# ProPrj_RGB_Controller_2025-11-02.net
KiCad netlist of a schematic drawn in EasyEDA Pro
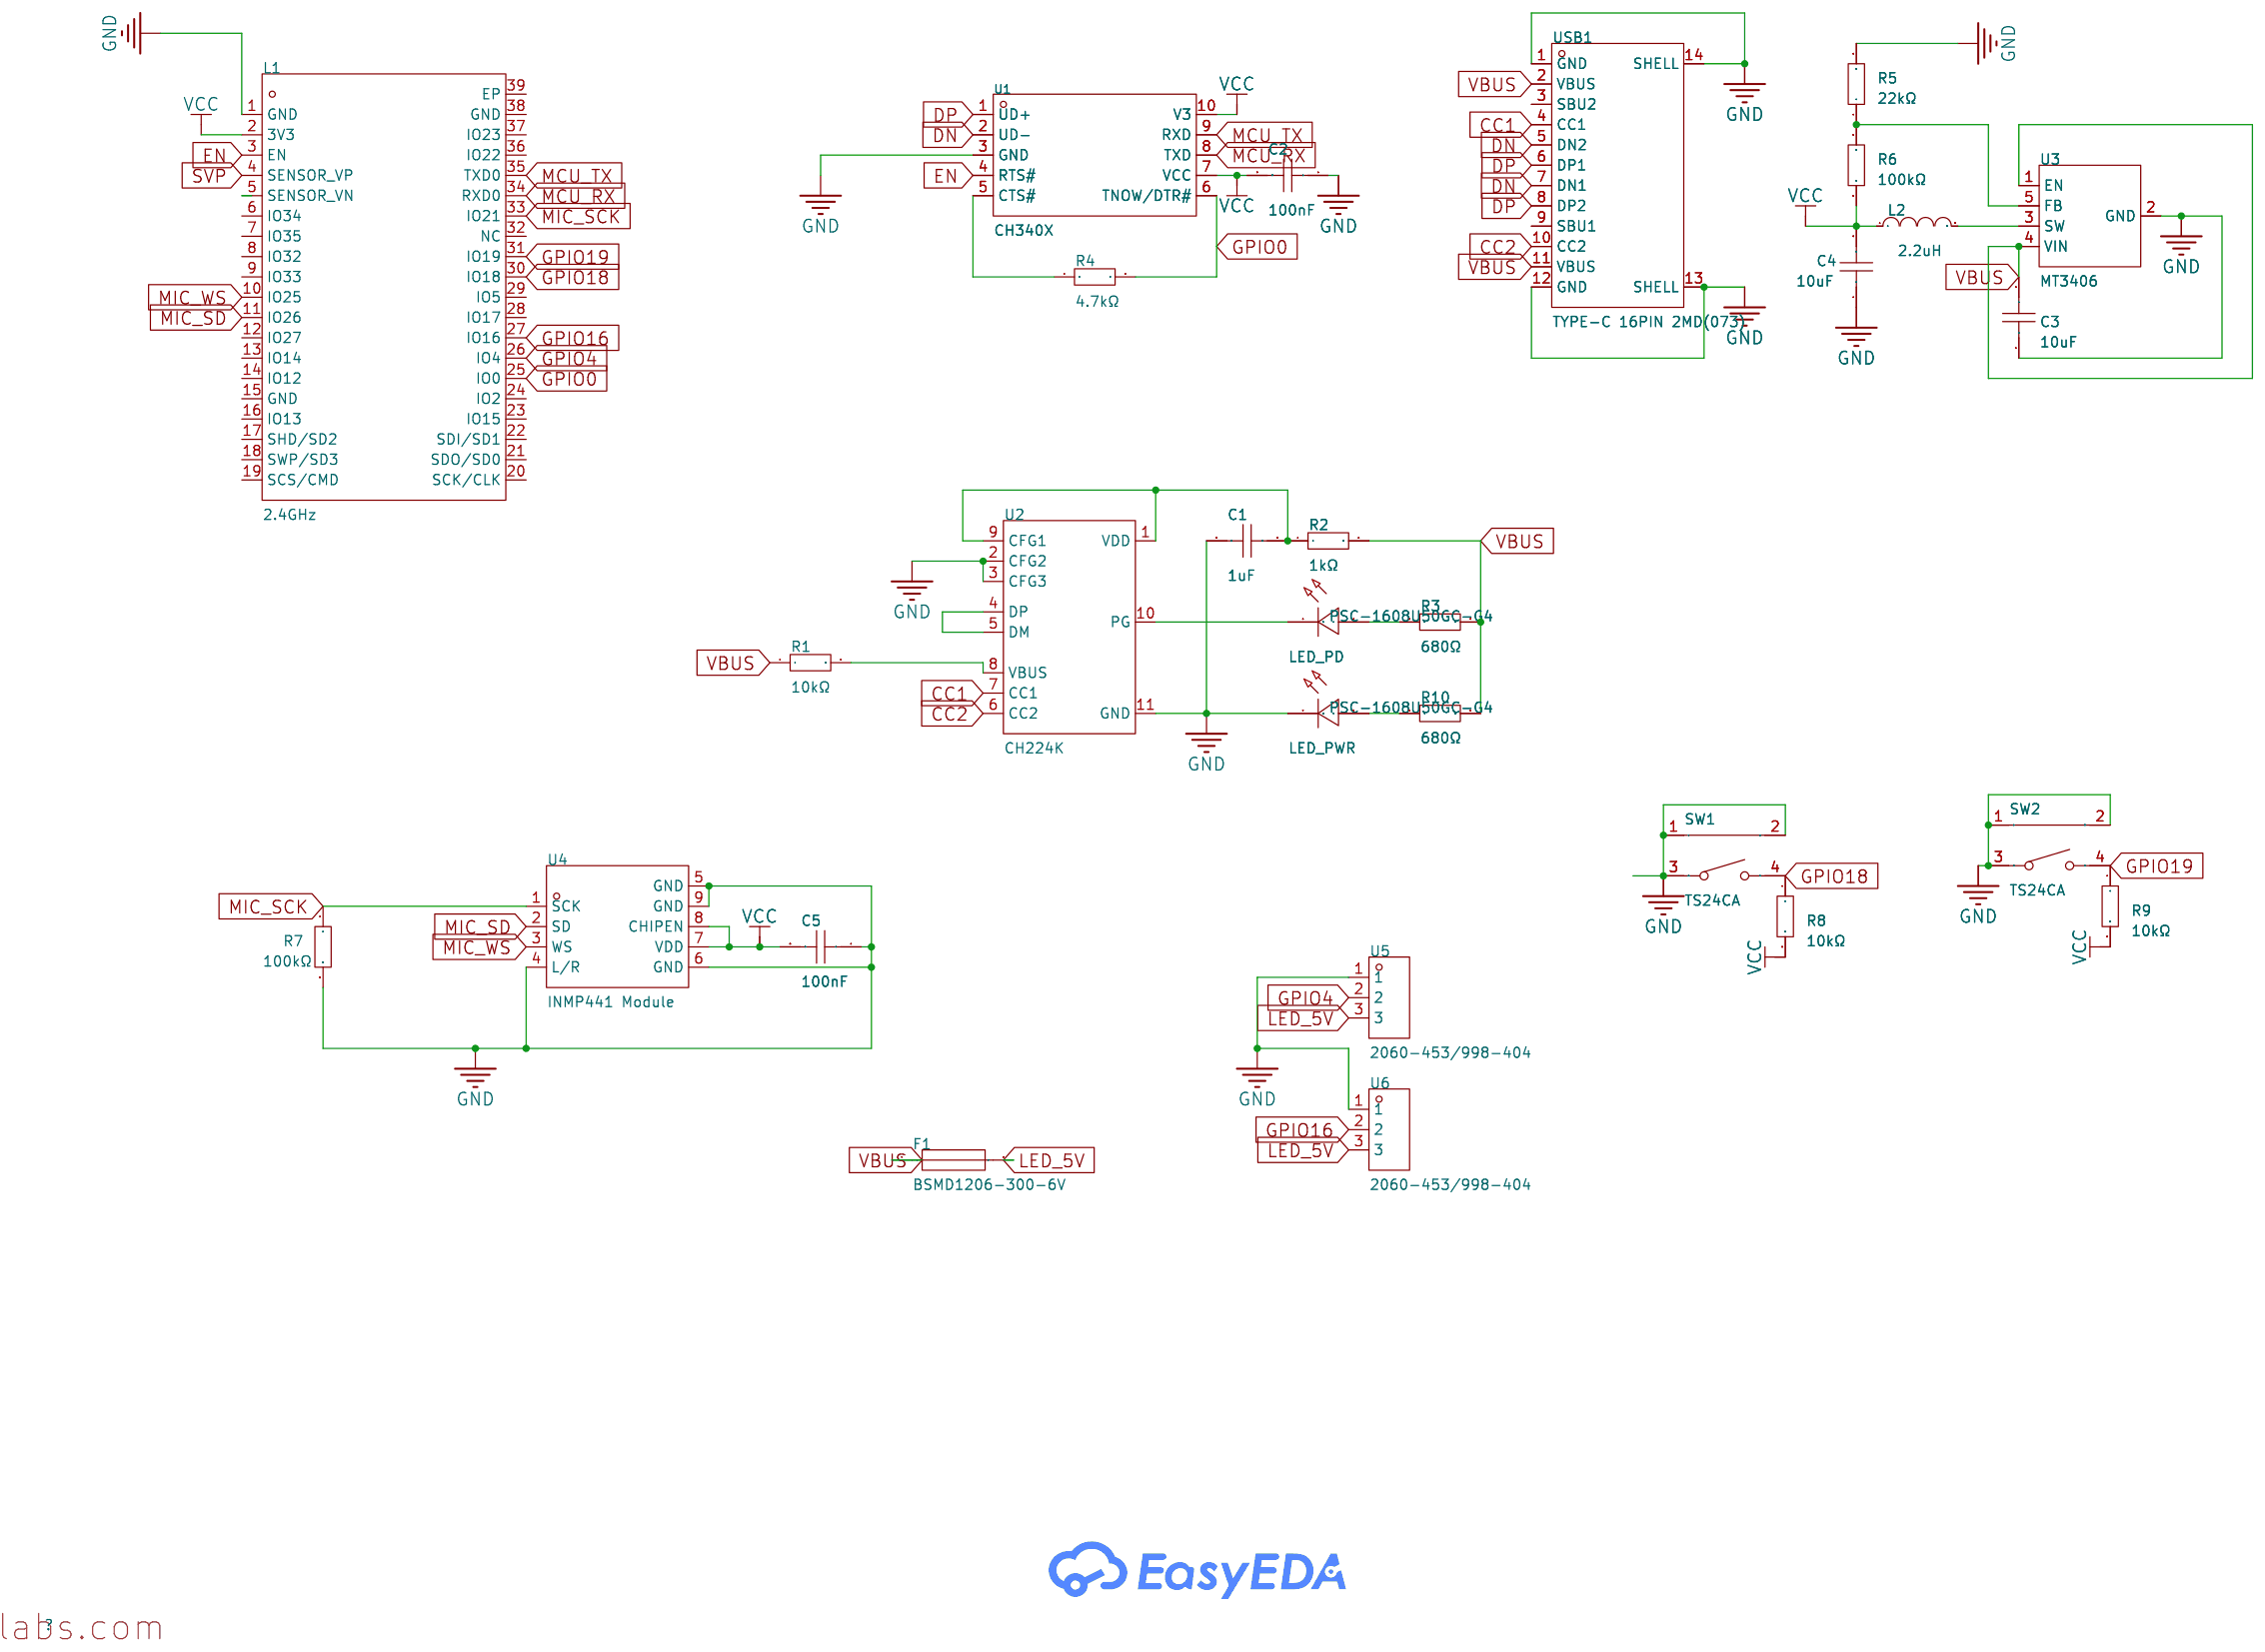
[diagram p0: schematic sheet]

(export (version "E")
  (design (tool "Eeschema 10.0.6"))
  (components
    (comp (ref "C1")
      (value "1uF")
      (footprint "easyedapro:C0603")
      (fields
        (field (name "Manufacturer Part") "CL05A105KO5NNNC")
        (field (name "Manufacturer") "SAMSUNG(三星)")
      )
      (libsource (lib "easyedapro") (part "CAP"))
    )
    (comp (ref "C2")
      (value "100nF")
      (footprint "easyedapro:C0603")
      (fields
        (field (name "Manufacturer Part") "CL05B104KO5NNNC")
        (field (name "Manufacturer") "SAMSUNG(三星)")
      )
      (libsource (lib "easyedapro") (part "CAP"))
    )
    (comp (ref "C3")
      (value "10uF")
      (footprint "easyedapro:C0603")
      (fields
        (field (name "Manufacturer Part") "CL10A106KP8NNNC")
        (field (name "Manufacturer") "SAMSUNG(三星)")
      )
      (libsource (lib "easyedapro") (part "CAP"))
    )
    (comp (ref "C4")
      (value "10uF")
      (footprint "easyedapro:C0603")
      (fields
        (field (name "Manufacturer Part") "CL10A106KP8NNNC")
        (field (name "Manufacturer") "SAMSUNG(三星)")
      )
      (libsource (lib "easyedapro") (part "CAP"))
    )
    (comp (ref "C5")
      (value "100nF")
      (footprint "easyedapro:C0603")
      (fields
        (field (name "Manufacturer Part") "CL05B104KO5NNNC")
        (field (name "Manufacturer") "SAMSUNG(三星)")
      )
      (libsource (lib "easyedapro") (part "CAP"))
    )
    (comp (ref "F1")
      (value "BSMD1206-300-6V")
      (footprint "easyedapro:F1206")
      (fields (field (name "Manufacturer") "BHFUSE(佰宏)"))
      (libsource (lib "easyedapro") (part "BSMD1206-300-6V"))
    )
    (comp (ref "L1")
      (value "2.4GHz")
      (footprint "easyedapro:WIFIM-SMD_ESP32-S32MB")
      (fields
        (field (name "Manufacturer Part") "ESP32-S32Mb")
        (field (name "Manufacturer") "Ai-Thinker(安信可)")
      )
      (libsource (lib "easyedapro") (part "ESP32-S32MB"))
    )
    (comp (ref "L2")
      (value "2.2uH")
      (footprint "easyedapro:L0603")
      (fields
        (field (name "Manufacturer Part") "FTC252012S2R2MBCA")
        (field (name "Manufacturer") "cjiang(长江微电)")
      )
      (libsource (lib "easyedapro") (part "电感"))
    )
    (comp (ref "LED_PD")
      (value "PSC-1608U50GC-G4")
      (footprint "easyedapro:LED0402-RD_YELLOW")
      (description "Emitted Color:Green")
      (fields (field (name "Manufacturer") "HONGLITRONIC(鸿利光电)"))
      (libsource (lib "easyedapro") (part "LED_G"))
    )
    (comp (ref "LED_PWR")
      (value "PSC-1608U50GC-G4")
      (footprint "easyedapro:LED0402-RD_YELLOW")
      (description "Emitted Color:Green")
      (fields (field (name "Manufacturer") "HONGLITRONIC(鸿利光电)"))
      (libsource (lib "easyedapro") (part "LED_G"))
    )
    (comp (ref "R1")
      (value "10kΩ")
      (footprint "easyedapro:R0603")
      (fields
        (field (name "Manufacturer Part") "0402WGF1002TCE")
        (field (name "Manufacturer") "UNI-ROYAL(厚声)")
      )
      (libsource (lib "easyedapro") (part "Res"))
    )
    (comp (ref "R2")
      (value "1kΩ")
      (footprint "easyedapro:R0603")
      (fields
        (field (name "Manufacturer Part") "0402WGF1001TCE")
        (field (name "Manufacturer") "UNI-ROYAL(厚声)")
      )
      (libsource (lib "easyedapro") (part "Res"))
    )
    (comp (ref "R3")
      (value "680Ω")
      (footprint "easyedapro:R0603")
      (fields
        (field (name "Manufacturer Part") "0402WGF6800TCE")
        (field (name "Manufacturer") "UNI-ROYAL(厚声)")
      )
      (libsource (lib "easyedapro") (part "Res"))
    )
    (comp (ref "R4")
      (value "4.7kΩ")
      (footprint "easyedapro:R0603")
      (fields
        (field (name "Manufacturer Part") "0402WGF4701TCE")
        (field (name "Manufacturer") "UNI-ROYAL(厚声)")
      )
      (libsource (lib "easyedapro") (part "Res"))
    )
    (comp (ref "R5")
      (value "22kΩ")
      (footprint "easyedapro:R0603")
      (fields
        (field (name "Manufacturer Part") "0402WGF2202TCE")
        (field (name "Manufacturer") "UNI-ROYAL(厚声)")
      )
      (libsource (lib "easyedapro") (part "Res"))
    )
    (comp (ref "R6")
      (value "100kΩ")
      (footprint "easyedapro:R0603")
      (fields
        (field (name "Manufacturer Part") "0402WGF1003TCE")
        (field (name "Manufacturer") "UNI-ROYAL(厚声)")
      )
      (libsource (lib "easyedapro") (part "Res"))
    )
    (comp (ref "R7")
      (value "100kΩ")
      (footprint "easyedapro:R0603")
      (fields
        (field (name "Manufacturer Part") "0402WGF1003TCE")
        (field (name "Manufacturer") "UNI-ROYAL(厚声)")
      )
      (libsource (lib "easyedapro") (part "Res"))
    )
    (comp (ref "R8")
      (value "10kΩ")
      (footprint "easyedapro:R0603")
      (fields
        (field (name "Manufacturer Part") "0402WGF1002TCE")
        (field (name "Manufacturer") "UNI-ROYAL(厚声)")
      )
      (libsource (lib "easyedapro") (part "Res"))
    )
    (comp (ref "R9")
      (value "10kΩ")
      (footprint "easyedapro:R0603")
      (fields
        (field (name "Manufacturer Part") "0402WGF1002TCE")
        (field (name "Manufacturer") "UNI-ROYAL(厚声)")
      )
      (libsource (lib "easyedapro") (part "Res"))
    )
    (comp (ref "R10")
      (value "680Ω")
      (footprint "easyedapro:R0603")
      (fields
        (field (name "Manufacturer Part") "0402WGF6800TCE")
        (field (name "Manufacturer") "UNI-ROYAL(厚声)")
      )
      (libsource (lib "easyedapro") (part "Res"))
    )
    (comp (ref "SW1")
      (value "TS24CA")
      (footprint "easyedapro:SW-SMD_TS24CA")
      (fields (field (name "Manufacturer") "SHOU HAN(首韩)"))
      (libsource (lib "easyedapro") (part "TS24CA"))
    )
    (comp (ref "SW2")
      (value "TS24CA")
      (footprint "easyedapro:SW-SMD_TS24CA")
      (fields (field (name "Manufacturer") "SHOU HAN(首韩)"))
      (libsource (lib "easyedapro") (part "TS24CA"))
    )
    (comp (ref "U1")
      (value "CH340X")
      (footprint "easyedapro:MSOP-10_L3.0-W3.0-P0.50-LS5.0-BL")
      (fields (field (name "Manufacturer") "WCH(南京沁恒)"))
      (libsource (lib "easyedapro") (part "CH340X"))
    )
    (comp (ref "U2")
      (value "CH224K")
      (footprint "easyedapro:ESSOP-10_L4.9-W3.9-P1.0-LS6.0-TL-EP")
      (fields (field (name "Manufacturer") "WCH(南京沁恒)"))
      (libsource (lib "easyedapro") (part "CH224K"))
    )
    (comp (ref "U3")
      (value "MT3406")
      (footprint "easyedapro:SOT-23-5_L2.9-W1.6-P0.95-LS2.8-BR")
      (fields (field (name "Manufacturer") "西安航天民芯"))
      (libsource (lib "easyedapro") (part "MT3406"))
    )
    (comp (ref "U4")
      (value "INMP441 Module")
      (footprint "easyedapro:MID-SMD_L4.7-W3.8_INMP441ACEZ")
      (libsource (lib "easyedapro") (part "INMP441 MODULE"))
    )
    (comp (ref "U5")
      (value "2060-453/998-404")
      (footprint "easyedapro:CONN-SMD_2060-453")
      (fields (field (name "Manufacturer") "WAGO(万可)"))
      (libsource (lib "easyedapro") (part "2060-453/998-404"))
    )
    (comp (ref "U6")
      (value "2060-453/998-404")
      (footprint "easyedapro:CONN-SMD_2060-453")
      (fields (field (name "Manufacturer") "WAGO(万可)"))
      (libsource (lib "easyedapro") (part "2060-453/998-404"))
    )
    (comp (ref "USB1")
      (value "TYPE-C 16PIN 2MD(073)")
      (footprint "easyedapro:USB-C-SMD_TYPE-C-6PIN-2MD-073")
      (fields (field (name "Manufacturer") "SHOU HAN(首韩)"))
      (libsource (lib "easyedapro") (part "TYPE-C 16PIN 2MD(073)"))
    )
  )
  (nets
    (net (code "1") (name "CC1") (class "Default")
      (node (ref "U2") (pin "7") (pinfunction "CC1_7") (pintype "unspecified"))
      (node (ref "USB1") (pin "4") (pinfunction "CC1_4") (pintype "unspecified"))
    )
    (net (code "2") (name "CC2") (class "Default")
      (node (ref "U2") (pin "6") (pinfunction "CC2_6") (pintype "unspecified"))
      (node (ref "USB1") (pin "10") (pinfunction "CC2_10") (pintype "unspecified"))
    )
    (net (code "3") (name "DN") (class "Default")
      (node (ref "U1") (pin "2") (pinfunction "UD-_2") (pintype "input"))
      (node (ref "USB1") (pin "5") (pinfunction "DN2_5") (pintype "unspecified"))
      (node (ref "USB1") (pin "7") (pinfunction "DN1_7") (pintype "unspecified"))
    )
    (net (code "4") (name "DP") (class "Default")
      (node (ref "U1") (pin "1") (pinfunction "UD+_1") (pintype "input"))
      (node (ref "USB1") (pin "6") (pinfunction "DP1_6") (pintype "unspecified"))
      (node (ref "USB1") (pin "8") (pinfunction "DP2_8") (pintype "unspecified"))
    )
    (net (code "5") (name "EN") (class "Default")
      (node (ref "L1") (pin "3") (pinfunction "EN_3") (pintype "input"))
      (node (ref "U1") (pin "4") (pinfunction "RTS#_4") (pintype "input"))
    )
    (net (code "6") (name "GND") (class "Default")
      (node (ref "C1") (pin "2") (pinfunction "2_2") (pintype "input"))
      (node (ref "C2") (pin "1") (pinfunction "1_1") (pintype "input"))
      (node (ref "C3") (pin "1") (pinfunction "1_1") (pintype "input"))
      (node (ref "C4") (pin "1") (pinfunction "1_1") (pintype "input"))
      (node (ref "C5") (pin "1") (pinfunction "1_1") (pintype "input"))
      (node (ref "L1") (pin "1") (pinfunction "GND_1") (pintype "input"))
      (node (ref "LED_PWR") (pin "1") (pinfunction "C_1") (pintype "input"))
      (node (ref "R5") (pin "2") (pinfunction "2_2") (pintype "input"))
      (node (ref "R7") (pin "2") (pinfunction "2_2") (pintype "input"))
      (node (ref "SW1") (pin "1") (pinfunction "1_1") (pintype "input"))
      (node (ref "SW1") (pin "2") (pinfunction "2_2") (pintype "input"))
      (node (ref "SW1") (pin "3") (pinfunction "3_3") (pintype "input"))
      (node (ref "SW2") (pin "1") (pinfunction "1_1") (pintype "input"))
      (node (ref "SW2") (pin "2") (pinfunction "2_2") (pintype "input"))
      (node (ref "SW2") (pin "3") (pinfunction "3_3") (pintype "input"))
      (node (ref "U1") (pin "3") (pinfunction "GND_3") (pintype "input"))
      (node (ref "U2") (pin "11") (pinfunction "GND_11") (pintype "unspecified"))
      (node (ref "U2") (pin "2") (pinfunction "CFG2_2") (pintype "unspecified"))
      (node (ref "U2") (pin "3") (pinfunction "CFG3_3") (pintype "unspecified"))
      (node (ref "U3") (pin "2") (pinfunction "GND_2") (pintype "unspecified"))
      (node (ref "U4") (pin "4") (pinfunction "L/R_4") (pintype "unspecified"))
      (node (ref "U4") (pin "5") (pinfunction "GND_5") (pintype "unspecified"))
      (node (ref "U4") (pin "6") (pinfunction "GND_6") (pintype "unspecified"))
      (node (ref "U4") (pin "9") (pinfunction "GND_9") (pintype "unspecified"))
      (node (ref "U5") (pin "1") (pinfunction "1_1") (pintype "unspecified"))
      (node (ref "U6") (pin "1") (pinfunction "1_1") (pintype "unspecified"))
      (node (ref "USB1") (pin "1") (pinfunction "GND_1") (pintype "unspecified"))
      (node (ref "USB1") (pin "12") (pinfunction "GND_12") (pintype "unspecified"))
      (node (ref "USB1") (pin "13") (pinfunction "SHELL_13") (pintype "unspecified"))
      (node (ref "USB1") (pin "14") (pinfunction "SHELL_14") (pintype "unspecified"))
    )
    (net (code "7") (name "GPIO0") (class "Default")
      (node (ref "L1") (pin "25") (pinfunction "IO0_25") (pintype "input"))
      (node (ref "R4") (pin "2") (pinfunction "2_2") (pintype "input"))
      (node (ref "U1") (pin "6") (pinfunction "TNOW/DTR#_6") (pintype "input"))
    )
    (net (code "8") (name "GPIO4") (class "Default")
      (node (ref "L1") (pin "26") (pinfunction "IO4_26") (pintype "input"))
      (node (ref "U5") (pin "2") (pinfunction "2_2") (pintype "unspecified"))
    )
    (net (code "9") (name "GPIO16") (class "Default")
      (node (ref "L1") (pin "27") (pinfunction "IO16_27") (pintype "input"))
      (node (ref "U6") (pin "2") (pinfunction "2_2") (pintype "unspecified"))
    )
    (net (code "10") (name "GPIO18") (class "Default")
      (node (ref "L1") (pin "30") (pinfunction "IO18_30") (pintype "input"))
      (node (ref "R8") (pin "1") (pinfunction "1_1") (pintype "input"))
      (node (ref "SW1") (pin "4") (pinfunction "4_4") (pintype "input"))
    )
    (net (code "11") (name "GPIO19") (class "Default")
      (node (ref "L1") (pin "31") (pinfunction "IO19_31") (pintype "input"))
      (node (ref "R9") (pin "1") (pinfunction "1_1") (pintype "input"))
      (node (ref "SW2") (pin "4") (pinfunction "4_4") (pintype "input"))
    )
    (net (code "12") (name "LED_5V") (class "Default")
      (node (ref "F1") (pin "2") (pinfunction "2_2") (pintype "unspecified"))
      (node (ref "U5") (pin "3") (pinfunction "3_3") (pintype "unspecified"))
      (node (ref "U6") (pin "3") (pinfunction "3_3") (pintype "unspecified"))
    )
    (net (code "13") (name "MCU_RX") (class "Default")
      (node (ref "L1") (pin "34") (pinfunction "RXD0_34") (pintype "input"))
      (node (ref "U1") (pin "8") (pinfunction "TXD_8") (pintype "input"))
    )
    (net (code "14") (name "MCU_TX") (class "Default")
      (node (ref "L1") (pin "35") (pinfunction "TXD0_35") (pintype "input"))
      (node (ref "U1") (pin "9") (pinfunction "RXD_9") (pintype "input"))
    )
    (net (code "15") (name "MIC_SCK") (class "Default")
      (node (ref "L1") (pin "33") (pinfunction "IO21_33") (pintype "input"))
      (node (ref "R7") (pin "1") (pinfunction "1_1") (pintype "input"))
      (node (ref "U4") (pin "1") (pinfunction "SCK_1") (pintype "unspecified"))
    )
    (net (code "16") (name "MIC_SD") (class "Default")
      (node (ref "L1") (pin "11") (pinfunction "IO26_11") (pintype "input"))
      (node (ref "U4") (pin "2") (pinfunction "SD_2") (pintype "unspecified"))
    )
    (net (code "17") (name "MIC_WS") (class "Default")
      (node (ref "L1") (pin "10") (pinfunction "IO25_10") (pintype "input"))
      (node (ref "U4") (pin "3") (pinfunction "WS_3") (pintype "unspecified"))
    )
    (net (code "18") (name "Net-(LED_PD-A)") (class "Default")
      (node (ref "LED_PD") (pin "2") (pinfunction "A_2") (pintype "input"))
      (node (ref "R3") (pin "1") (pinfunction "1_1") (pintype "input"))
    )
    (net (code "19") (name "Net-(LED_PD-C)") (class "Default")
      (node (ref "LED_PD") (pin "1") (pinfunction "C_1") (pintype "input"))
      (node (ref "U2") (pin "10") (pinfunction "PG_10") (pintype "unspecified"))
    )
    (net (code "20") (name "Net-(LED_PWR-A)") (class "Default")
      (node (ref "LED_PWR") (pin "2") (pinfunction "A_2") (pintype "input"))
      (node (ref "R10") (pin "1") (pinfunction "1_1") (pintype "input"))
    )
    (net (code "21") (name "Net-(U1-CTS#)") (class "Default")
      (node (ref "R4") (pin "1") (pinfunction "1_1") (pintype "input"))
      (node (ref "U1") (pin "5") (pinfunction "CTS#_5") (pintype "input"))
    )
    (net (code "22") (name "Net-(U2-CFG1)") (class "Default")
      (node (ref "C1") (pin "1") (pinfunction "1_1") (pintype "input"))
      (node (ref "R2") (pin "1") (pinfunction "1_1") (pintype "input"))
      (node (ref "U2") (pin "1") (pinfunction "VDD_1") (pintype "unspecified"))
      (node (ref "U2") (pin "9") (pinfunction "CFG1_9") (pintype "unspecified"))
    )
    (net (code "23") (name "Net-(U2-DM)") (class "Default")
      (node (ref "U2") (pin "4") (pinfunction "DP_4") (pintype "unspecified"))
      (node (ref "U2") (pin "5") (pinfunction "DM_5") (pintype "unspecified"))
    )
    (net (code "24") (name "Net-(U2-VBUS)") (class "Default")
      (node (ref "R1") (pin "2") (pinfunction "2_2") (pintype "input"))
      (node (ref "U2") (pin "8") (pinfunction "VBUS_8") (pintype "unspecified"))
    )
    (net (code "25") (name "Net-(U3-FB)") (class "Default")
      (node (ref "R5") (pin "1") (pinfunction "1_1") (pintype "input"))
      (node (ref "R6") (pin "1") (pinfunction "1_1") (pintype "input"))
      (node (ref "U3") (pin "5") (pinfunction "FB_5") (pintype "unspecified"))
    )
    (net (code "26") (name "Net-(U3-SW)") (class "Default")
      (node (ref "L2") (pin "2") (pinfunction "2_2") (pintype "input"))
      (node (ref "U3") (pin "3") (pinfunction "SW_3") (pintype "unspecified"))
    )
    (net (code "27") (name "SVP") (class "Default")
      (node (ref "L1") (pin "4") (pinfunction "SENSOR_VP_4") (pintype "input"))
    )
    (net (code "28") (name "VBUS") (class "Default")
      (node (ref "C3") (pin "2") (pinfunction "2_2") (pintype "input"))
      (node (ref "F1") (pin "1") (pinfunction "1_1") (pintype "unspecified"))
      (node (ref "R1") (pin "1") (pinfunction "1_1") (pintype "input"))
      (node (ref "R10") (pin "2") (pinfunction "2_2") (pintype "input"))
      (node (ref "R2") (pin "2") (pinfunction "2_2") (pintype "input"))
      (node (ref "R3") (pin "2") (pinfunction "2_2") (pintype "input"))
      (node (ref "U3") (pin "1") (pinfunction "EN_1") (pintype "unspecified"))
      (node (ref "U3") (pin "4") (pinfunction "VIN_4") (pintype "unspecified"))
      (node (ref "USB1") (pin "11") (pinfunction "VBUS_11") (pintype "unspecified"))
      (node (ref "USB1") (pin "2") (pinfunction "VBUS_2") (pintype "unspecified"))
    )
    (net (code "29") (name "VCC") (class "Default")
      (node (ref "C2") (pin "2") (pinfunction "2_2") (pintype "input"))
      (node (ref "C4") (pin "2") (pinfunction "2_2") (pintype "input"))
      (node (ref "C5") (pin "2") (pinfunction "2_2") (pintype "input"))
      (node (ref "L1") (pin "2") (pinfunction "3V3_2") (pintype "input"))
      (node (ref "L2") (pin "1") (pinfunction "1_1") (pintype "input"))
      (node (ref "R6") (pin "2") (pinfunction "2_2") (pintype "input"))
      (node (ref "R8") (pin "2") (pinfunction "2_2") (pintype "input"))
      (node (ref "R9") (pin "2") (pinfunction "2_2") (pintype "input"))
      (node (ref "U1") (pin "10") (pinfunction "V3_10") (pintype "input"))
      (node (ref "U1") (pin "7") (pinfunction "VCC_7") (pintype "input"))
      (node (ref "U4") (pin "7") (pinfunction "VDD_7") (pintype "unspecified"))
      (node (ref "U4") (pin "8") (pinfunction "CHIPEN_8") (pintype "unspecified"))
    )
    (net (code "30") (name "unconnected-(L1-EP-Pad39)") (class "Default")
      (node (ref "L1") (pin "39") (pinfunction "EP_39") (pintype "input"))
    )
    (net (code "31") (name "unconnected-(L1-GND-Pad15)") (class "Default")
      (node (ref "L1") (pin "15") (pinfunction "GND_15") (pintype "input"))
    )
    (net (code "32") (name "unconnected-(L1-GND-Pad38)") (class "Default")
      (node (ref "L1") (pin "38") (pinfunction "GND_38") (pintype "input"))
    )
    (net (code "33") (name "unconnected-(L1-IO2-Pad24)") (class "Default")
      (node (ref "L1") (pin "24") (pinfunction "IO2_24") (pintype "input"))
    )
    (net (code "34") (name "unconnected-(L1-IO5-Pad29)") (class "Default")
      (node (ref "L1") (pin "29") (pinfunction "IO5_29") (pintype "input"))
    )
    (net (code "35") (name "unconnected-(L1-IO12-Pad14)") (class "Default")
      (node (ref "L1") (pin "14") (pinfunction "IO12_14") (pintype "input"))
    )
    (net (code "36") (name "unconnected-(L1-IO13-Pad16)") (class "Default")
      (node (ref "L1") (pin "16") (pinfunction "IO13_16") (pintype "input"))
    )
    (net (code "37") (name "unconnected-(L1-IO14-Pad13)") (class "Default")
      (node (ref "L1") (pin "13") (pinfunction "IO14_13") (pintype "input"))
    )
    (net (code "38") (name "unconnected-(L1-IO15-Pad23)") (class "Default")
      (node (ref "L1") (pin "23") (pinfunction "IO15_23") (pintype "input"))
    )
    (net (code "39") (name "unconnected-(L1-IO17-Pad28)") (class "Default")
      (node (ref "L1") (pin "28") (pinfunction "IO17_28") (pintype "input"))
    )
    (net (code "40") (name "unconnected-(L1-IO22-Pad36)") (class "Default")
      (node (ref "L1") (pin "36") (pinfunction "IO22_36") (pintype "input"))
    )
    (net (code "41") (name "unconnected-(L1-IO23-Pad37)") (class "Default")
      (node (ref "L1") (pin "37") (pinfunction "IO23_37") (pintype "input"))
    )
    (net (code "42") (name "unconnected-(L1-IO27-Pad12)") (class "Default")
      (node (ref "L1") (pin "12") (pinfunction "IO27_12") (pintype "input"))
    )
    (net (code "43") (name "unconnected-(L1-IO32-Pad8)") (class "Default")
      (node (ref "L1") (pin "8") (pinfunction "IO32_8") (pintype "input"))
    )
    (net (code "44") (name "unconnected-(L1-IO33-Pad9)") (class "Default")
      (node (ref "L1") (pin "9") (pinfunction "IO33_9") (pintype "input"))
    )
    (net (code "45") (name "unconnected-(L1-IO34-Pad6)") (class "Default")
      (node (ref "L1") (pin "6") (pinfunction "IO34_6") (pintype "input"))
    )
    (net (code "46") (name "unconnected-(L1-IO35-Pad7)") (class "Default")
      (node (ref "L1") (pin "7") (pinfunction "IO35_7") (pintype "input"))
    )
    (net (code "47") (name "unconnected-(L1-NC-Pad32)") (class "Default")
      (node (ref "L1") (pin "32") (pinfunction "NC_32") (pintype "input"))
    )
    (net (code "48") (name "unconnected-(L1-SCK{slash}CLK-Pad20)") (class "Default")
      (node (ref "L1") (pin "20") (pinfunction "SCK/CLK_20") (pintype "input"))
    )
    (net (code "49") (name "unconnected-(L1-SCS{slash}CMD-Pad19)") (class "Default")
      (node (ref "L1") (pin "19") (pinfunction "SCS/CMD_19") (pintype "input"))
    )
    (net (code "50") (name "unconnected-(L1-SDI{slash}SD1-Pad22)") (class "Default")
      (node (ref "L1") (pin "22") (pinfunction "SDI/SD1_22") (pintype "input"))
    )
    (net (code "51") (name "unconnected-(L1-SDO{slash}SD0-Pad21)") (class "Default")
      (node (ref "L1") (pin "21") (pinfunction "SDO/SD0_21") (pintype "input"))
    )
    (net (code "52") (name "unconnected-(L1-SENSOR_VN-Pad5)") (class "Default")
      (node (ref "L1") (pin "5") (pinfunction "SENSOR_VN_5") (pintype "input"))
    )
    (net (code "53") (name "unconnected-(L1-SHD{slash}SD2-Pad17)") (class "Default")
      (node (ref "L1") (pin "17") (pinfunction "SHD/SD2_17") (pintype "input"))
    )
    (net (code "54") (name "unconnected-(L1-SWP{slash}SD3-Pad18)") (class "Default")
      (node (ref "L1") (pin "18") (pinfunction "SWP/SD3_18") (pintype "input"))
    )
    (net (code "55") (name "unconnected-(USB1-SBU1-Pad9)") (class "Default")
      (node (ref "USB1") (pin "9") (pinfunction "SBU1_9") (pintype "unspecified"))
    )
    (net (code "56") (name "unconnected-(USB1-SBU2-Pad3)") (class "Default")
      (node (ref "USB1") (pin "3") (pinfunction "SBU2_3") (pintype "unspecified"))
    )
  )
)
